# PowerGlove_DueShield.net
KiCad netlist of a schematic drawn in EAGLE
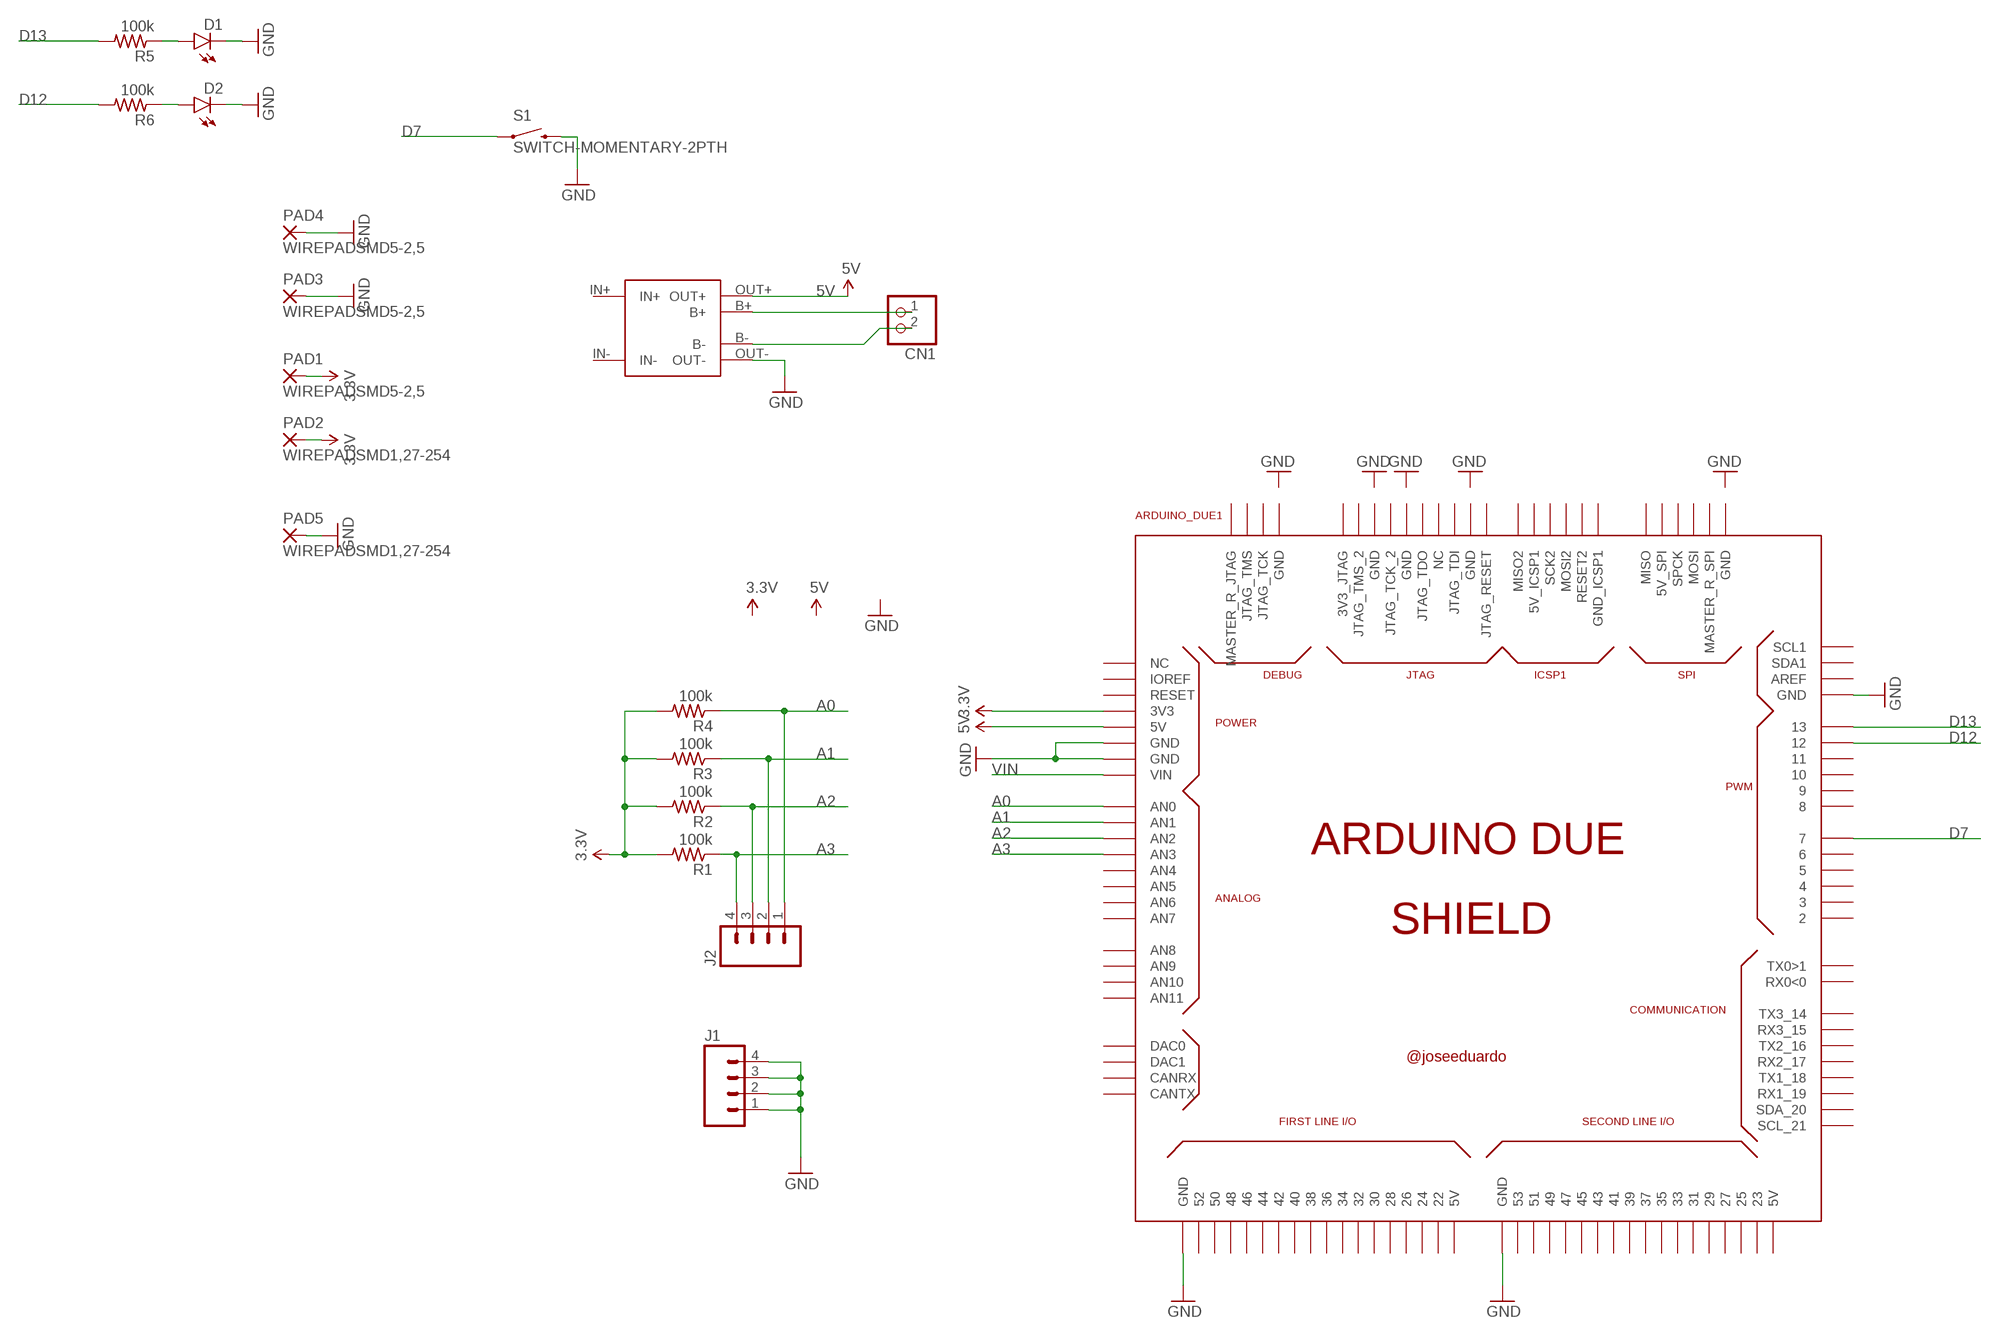
[diagram p0: schematic, sheet 1]

(export (version "E")
  (design (tool "Eeschema 10.0.6"))
  (components
    (comp (ref "ARDUINO_DUE1")
      (value "ARDUINO_DUE_SHIELD")
      (footprint "eagle-import:ARDUINO_DUE_SHIELD")
      (libsource (lib "eagle-import") (part "ARDUINO_DUE_SHIELD"))
    )
    (comp (ref "CN1")
      (value "JST_2PIN-THM-RA")
      (footprint "eagle-import:JST-PH-2-THM-RA")
      (libsource (lib "eagle-import") (part "JST_2PIN-THM-RA"))
    )
    (comp (ref "D1")
      (value "LED3MM")
      (footprint "eagle-import:LED3MM")
      (libsource (lib "eagle-import") (part "LED3MM"))
    )
    (comp (ref "D2")
      (value "LED3MM")
      (footprint "eagle-import:LED3MM")
      (libsource (lib "eagle-import") (part "LED3MM"))
    )
    (comp (ref "J1")
      (value "M04LONGPADS")
      (footprint "eagle-import:1X04_LONGPADS")
      (libsource (lib "eagle-import") (part "M04LONGPADS"))
    )
    (comp (ref "J2")
      (value "M04LONGPADS")
      (footprint "eagle-import:1X04_LONGPADS")
      (libsource (lib "eagle-import") (part "M04LONGPADS"))
    )
    (comp (ref "PAD1")
      (value "WIREPADSMD5-2,5")
      (footprint "eagle-import:5-2,5")
      (libsource (lib "eagle-import") (part "WIREPADSMD5-2,5"))
    )
    (comp (ref "PAD2")
      (value "WIREPADSMD1,27-254")
      (footprint "eagle-import:SMD1,27-2,54")
      (libsource (lib "eagle-import") (part "WIREPADSMD1,27-254"))
    )
    (comp (ref "PAD3")
      (value "WIREPADSMD5-2,5")
      (footprint "eagle-import:5-2,5")
      (libsource (lib "eagle-import") (part "WIREPADSMD5-2,5"))
    )
    (comp (ref "PAD4")
      (value "WIREPADSMD5-2,5")
      (footprint "eagle-import:5-2,5")
      (libsource (lib "eagle-import") (part "WIREPADSMD5-2,5"))
    )
    (comp (ref "PAD5")
      (value "WIREPADSMD1,27-254")
      (footprint "eagle-import:SMD1,27-2,54")
      (libsource (lib "eagle-import") (part "WIREPADSMD1,27-254"))
    )
    (comp (ref "R1")
      (value "100k")
      (footprint "eagle-import:0207_10")
      (libsource (lib "eagle-import") (part "R-US_0207/10"))
    )
    (comp (ref "R2")
      (value "100k")
      (footprint "eagle-import:0207_10")
      (libsource (lib "eagle-import") (part "R-US_0207/10"))
    )
    (comp (ref "R3")
      (value "100k")
      (footprint "eagle-import:0207_10")
      (libsource (lib "eagle-import") (part "R-US_0207/10"))
    )
    (comp (ref "R4")
      (value "100k")
      (footprint "eagle-import:0207_10")
      (libsource (lib "eagle-import") (part "R-US_0207/10"))
    )
    (comp (ref "R5")
      (value "100k")
      (footprint "eagle-import:0207_10")
      (libsource (lib "eagle-import") (part "R-US_0207/10"))
    )
    (comp (ref "R6")
      (value "100k")
      (footprint "eagle-import:0207_10")
      (libsource (lib "eagle-import") (part "R-US_0207/10"))
    )
    (comp (ref "S1")
      (value "SWITCH-MOMENTARY-2PTH")
      (footprint "eagle-import:TACTILE-PTH")
      (libsource (lib "eagle-import") (part "SWITCH-MOMENTARY-2PTH"))
    )
    (comp (ref "U$1")
      (value "TP4056-MODULE")
      (footprint "eagle-import:TP4056-LITHIUM-PROTECTED-MODULE")
      (libsource (lib "eagle-import") (part "TP4056-MODULE"))
    )
  )
  (nets
    (net (code "1") (name "/A0") (class "Default")
      (node (ref "ARDUINO_DUE1") (pin "A0") (pinfunction "AN0_A0") (pintype "bidirectional"))
      (node (ref "J2") (pin "1") (pinfunction "1_1") (pintype "passive"))
      (node (ref "R4") (pin "1") (pinfunction "1_1") (pintype "passive"))
    )
    (net (code "2") (name "/A1") (class "Default")
      (node (ref "ARDUINO_DUE1") (pin "A1") (pinfunction "AN1_A1") (pintype "bidirectional"))
      (node (ref "J2") (pin "2") (pinfunction "2_2") (pintype "passive"))
      (node (ref "R3") (pin "1") (pinfunction "1_1") (pintype "passive"))
    )
    (net (code "3") (name "/A2") (class "Default")
      (node (ref "ARDUINO_DUE1") (pin "A2") (pinfunction "AN2_A2") (pintype "bidirectional"))
      (node (ref "J2") (pin "3") (pinfunction "3_3") (pintype "passive"))
      (node (ref "R2") (pin "1") (pinfunction "1_1") (pintype "passive"))
    )
    (net (code "4") (name "/A3") (class "Default")
      (node (ref "ARDUINO_DUE1") (pin "A3") (pinfunction "AN3_A3") (pintype "bidirectional"))
      (node (ref "J2") (pin "4") (pinfunction "4_4") (pintype "passive"))
      (node (ref "R1") (pin "1") (pinfunction "1_1") (pintype "passive"))
    )
    (net (code "5") (name "/D7") (class "Default")
      (node (ref "ARDUINO_DUE1") (pin "7") (pinfunction "7_7") (pintype "bidirectional"))
      (node (ref "S1") (pin "1") (pinfunction "1_1") (pintype "passive"))
    )
    (net (code "6") (name "/D12") (class "Default")
      (node (ref "ARDUINO_DUE1") (pin "12") (pinfunction "12_12") (pintype "bidirectional"))
      (node (ref "R6") (pin "2") (pinfunction "2_2") (pintype "passive"))
    )
    (net (code "7") (name "/D13") (class "Default")
      (node (ref "ARDUINO_DUE1") (pin "13") (pinfunction "13_13") (pintype "bidirectional"))
      (node (ref "R5") (pin "2") (pinfunction "2_2") (pintype "passive"))
    )
    (net (code "8") (name "/IN+") (class "Default")
      (node (ref "U$1") (pin "IN+") (pinfunction "IN+_IN+") (pintype "power_in"))
    )
    (net (code "9") (name "/IN-") (class "Default")
      (node (ref "U$1") (pin "IN-") (pinfunction "IN-_IN-") (pintype "power_in"))
    )
    (net (code "10") (name "/VIN") (class "Default")
      (node (ref "ARDUINO_DUE1") (pin "VIN") (pinfunction "VIN_VIN") (pintype "bidirectional"))
    )
    (net (code "11") (name "3.3V") (class "Default")
      (node (ref "ARDUINO_DUE1") (pin "3V3") (pinfunction "3V3_3V3") (pintype "bidirectional"))
      (node (ref "PAD1") (pin "1") (pinfunction "P_1") (pintype "passive"))
      (node (ref "PAD2") (pin "1") (pinfunction "P_1") (pintype "passive"))
      (node (ref "R1") (pin "2") (pinfunction "2_2") (pintype "passive"))
      (node (ref "R2") (pin "2") (pinfunction "2_2") (pintype "passive"))
      (node (ref "R3") (pin "2") (pinfunction "2_2") (pintype "passive"))
      (node (ref "R4") (pin "2") (pinfunction "2_2") (pintype "passive"))
    )
    (net (code "12") (name "5V") (class "Default")
      (node (ref "ARDUINO_DUE1") (pin "5V0") (pinfunction "5V_5V0") (pintype "bidirectional"))
      (node (ref "U$1") (pin "OUT+") (pinfunction "OUT+_OUT+") (pintype "power_in"))
    )
    (net (code "13") (name "GND") (class "Default")
      (node (ref "ARDUINO_DUE1") (pin "GND") (pinfunction "GND_GND") (pintype "bidirectional"))
      (node (ref "ARDUINO_DUE1") (pin "GND_1") (pinfunction "GND_GND_1") (pintype "bidirectional"))
      (node (ref "ARDUINO_DUE1") (pin "GND_2") (pinfunction "GND_GND_2") (pintype "bidirectional"))
      (node (ref "ARDUINO_DUE1") (pin "GND_3") (pinfunction "GND_GND_3") (pintype "bidirectional"))
      (node (ref "ARDUINO_DUE1") (pin "GND_4") (pinfunction "GND_GND_4") (pintype "bidirectional"))
      (node (ref "D1") (pin "K") (pinfunction "C_K") (pintype "passive"))
      (node (ref "D2") (pin "K") (pinfunction "C_K") (pintype "passive"))
      (node (ref "J1") (pin "1") (pinfunction "1_1") (pintype "passive"))
      (node (ref "J1") (pin "2") (pinfunction "2_2") (pintype "passive"))
      (node (ref "J1") (pin "3") (pinfunction "3_3") (pintype "passive"))
      (node (ref "J1") (pin "4") (pinfunction "4_4") (pintype "passive"))
      (node (ref "PAD3") (pin "1") (pinfunction "P_1") (pintype "passive"))
      (node (ref "PAD4") (pin "1") (pinfunction "P_1") (pintype "passive"))
      (node (ref "PAD5") (pin "1") (pinfunction "P_1") (pintype "passive"))
      (node (ref "S1") (pin "3") (pinfunction "2_3") (pintype "passive"))
      (node (ref "U$1") (pin "OUT-") (pinfunction "OUT-_OUT-") (pintype "power_in"))
    )
    (net (code "14") (name "Net-(CN1-1)") (class "Default")
      (node (ref "CN1") (pin "2") (pinfunction "1_2") (pintype "passive"))
      (node (ref "U$1") (pin "B-") (pinfunction "B-_B-") (pintype "power_in"))
    )
    (net (code "15") (name "Net-(CN1-2)") (class "Default")
      (node (ref "CN1") (pin "1") (pinfunction "2_1") (pintype "passive"))
      (node (ref "U$1") (pin "B+") (pinfunction "B+_B+") (pintype "power_in"))
    )
    (net (code "16") (name "Net-(D1-PadA)") (class "Default")
      (node (ref "D1") (pin "A") (pinfunction "A_A") (pintype "passive"))
      (node (ref "R5") (pin "1") (pinfunction "1_1") (pintype "passive"))
    )
    (net (code "17") (name "Net-(D2-PadA)") (class "Default")
      (node (ref "D2") (pin "A") (pinfunction "A_A") (pintype "passive"))
      (node (ref "R6") (pin "1") (pinfunction "1_1") (pintype "passive"))
    )
    (net (code "18") (name "unconnected-(ARDUINO_DUE1-5V-Pad5V0_1)") (class "Default")
      (node (ref "ARDUINO_DUE1") (pin "5V0_1") (pinfunction "5V_5V0_1") (pintype "bidirectional"))
    )
    (net (code "19") (name "unconnected-(ARDUINO_DUE1-5V-Pad5V0_2)") (class "Default")
      (node (ref "ARDUINO_DUE1") (pin "5V0_2") (pinfunction "5V_5V0_2") (pintype "bidirectional"))
    )
    (net (code "20") (name "unconnected-(ARDUINO_DUE1-5V_SPI-Pad5V_2)") (class "Default")
      (node (ref "ARDUINO_DUE1") (pin "5V_2") (pinfunction "5V_SPI_5V_2") (pintype "bidirectional"))
    )
    (net (code "21") (name "unconnected-(ARDUINO_DUE1-AN4-PadA4)") (class "Default")
      (node (ref "ARDUINO_DUE1") (pin "A4") (pinfunction "AN4_A4") (pintype "bidirectional"))
    )
    (net (code "22") (name "unconnected-(ARDUINO_DUE1-AN5-PadA5)") (class "Default")
      (node (ref "ARDUINO_DUE1") (pin "A5") (pinfunction "AN5_A5") (pintype "bidirectional"))
    )
    (net (code "23") (name "unconnected-(ARDUINO_DUE1-AN6-PadA6)") (class "Default")
      (node (ref "ARDUINO_DUE1") (pin "A6") (pinfunction "AN6_A6") (pintype "bidirectional"))
    )
    (net (code "24") (name "unconnected-(ARDUINO_DUE1-AN7-PadA7)") (class "Default")
      (node (ref "ARDUINO_DUE1") (pin "A7") (pinfunction "AN7_A7") (pintype "bidirectional"))
    )
    (net (code "25") (name "unconnected-(ARDUINO_DUE1-AN8-PadA8)") (class "Default")
      (node (ref "ARDUINO_DUE1") (pin "A8") (pinfunction "AN8_A8") (pintype "bidirectional"))
    )
    (net (code "26") (name "unconnected-(ARDUINO_DUE1-AN9-PadA9)") (class "Default")
      (node (ref "ARDUINO_DUE1") (pin "A9") (pinfunction "AN9_A9") (pintype "bidirectional"))
    )
    (net (code "27") (name "unconnected-(ARDUINO_DUE1-AN10-PadA10)") (class "Default")
      (node (ref "ARDUINO_DUE1") (pin "A10") (pinfunction "AN10_A10") (pintype "bidirectional"))
    )
    (net (code "28") (name "unconnected-(ARDUINO_DUE1-AN11-PadA11)") (class "Default")
      (node (ref "ARDUINO_DUE1") (pin "A11") (pinfunction "AN11_A11") (pintype "bidirectional"))
    )
    (net (code "29") (name "unconnected-(ARDUINO_DUE1-GND-PadGND_5)") (class "Default")
      (node (ref "ARDUINO_DUE1") (pin "GND_5") (pinfunction "GND_GND_5") (pintype "bidirectional"))
    )
    (net (code "30") (name "unconnected-(ARDUINO_DUE1-GND-PadGND_7)") (class "Default")
      (node (ref "ARDUINO_DUE1") (pin "GND_7") (pinfunction "GND_GND_7") (pintype "bidirectional"))
    )
    (net (code "31") (name "unconnected-(ARDUINO_DUE1-GND-PadGND_8)") (class "Default")
      (node (ref "ARDUINO_DUE1") (pin "GND_8") (pinfunction "GND_GND_8") (pintype "bidirectional"))
    )
    (net (code "32") (name "unconnected-(ARDUINO_DUE1-GND-PadGND_9)") (class "Default")
      (node (ref "ARDUINO_DUE1") (pin "GND_9") (pinfunction "GND_GND_9") (pintype "bidirectional"))
    )
    (net (code "33") (name "unconnected-(ARDUINO_DUE1-GND-PadGND_10)") (class "Default")
      (node (ref "ARDUINO_DUE1") (pin "GND_10") (pinfunction "GND_GND_10") (pintype "bidirectional"))
    )
    (net (code "34") (name "unconnected-(ARDUINO_DUE1-MASTER_R_JTAG-PadMASTER_RESET_JTAG)") (class "Default")
      (node (ref "ARDUINO_DUE1") (pin "MASTER_RESET_JTAG") (pinfunction "MASTER_R_JTAG_MASTER_RESET_JTAG") (pintype "bidirectional"))
    )
    (net (code "35") (name "unconnected-(ARDUINO_DUE1-MASTER_R_SPI-PadMASTER_RESET_SPI)") (class "Default")
      (node (ref "ARDUINO_DUE1") (pin "MASTER_RESET_SPI") (pinfunction "MASTER_R_SPI_MASTER_RESET_SPI") (pintype "bidirectional"))
    )
    (net (code "36") (name "unconnected-(ARDUINO_DUE1-NC-PadNC_2)") (class "Default")
      (node (ref "ARDUINO_DUE1") (pin "NC_2") (pinfunction "NC_NC_2") (pintype "no_connect"))
    )
    (net (code "37") (name "unconnected-(ARDUINO_DUE1-NC-PadNC_5)") (class "Default")
      (node (ref "ARDUINO_DUE1") (pin "NC_5") (pinfunction "NC_NC_5") (pintype "bidirectional"))
    )
    (net (code "38") (name "unconnected-(ARDUINO_DUE1-Pad2)") (class "Default")
      (node (ref "ARDUINO_DUE1") (pin "2") (pinfunction "2_2") (pintype "bidirectional"))
    )
    (net (code "39") (name "unconnected-(ARDUINO_DUE1-Pad3)") (class "Default")
      (node (ref "ARDUINO_DUE1") (pin "3") (pinfunction "3_3") (pintype "bidirectional"))
    )
    (net (code "40") (name "unconnected-(ARDUINO_DUE1-Pad3V3_JTAG)") (class "Default")
      (node (ref "ARDUINO_DUE1") (pin "3V3_JTAG") (pinfunction "3V3_JTAG_3V3_JTAG") (pintype "bidirectional"))
    )
    (net (code "41") (name "unconnected-(ARDUINO_DUE1-Pad4)") (class "Default")
      (node (ref "ARDUINO_DUE1") (pin "4") (pinfunction "4_4") (pintype "bidirectional"))
    )
    (net (code "42") (name "unconnected-(ARDUINO_DUE1-Pad5)") (class "Default")
      (node (ref "ARDUINO_DUE1") (pin "5") (pinfunction "5_5") (pintype "bidirectional"))
    )
    (net (code "43") (name "unconnected-(ARDUINO_DUE1-Pad5V_ICSP1)") (class "Default")
      (node (ref "ARDUINO_DUE1") (pin "5V_ICSP1") (pinfunction "5V_ICSP1_5V_ICSP1") (pintype "bidirectional"))
    )
    (net (code "44") (name "unconnected-(ARDUINO_DUE1-Pad6)") (class "Default")
      (node (ref "ARDUINO_DUE1") (pin "6") (pinfunction "6_6") (pintype "bidirectional"))
    )
    (net (code "45") (name "unconnected-(ARDUINO_DUE1-Pad8)") (class "Default")
      (node (ref "ARDUINO_DUE1") (pin "8") (pinfunction "8_8") (pintype "bidirectional"))
    )
    (net (code "46") (name "unconnected-(ARDUINO_DUE1-Pad9)") (class "Default")
      (node (ref "ARDUINO_DUE1") (pin "9") (pinfunction "9_9") (pintype "bidirectional"))
    )
    (net (code "47") (name "unconnected-(ARDUINO_DUE1-Pad10)") (class "Default")
      (node (ref "ARDUINO_DUE1") (pin "10") (pinfunction "10_10") (pintype "bidirectional"))
    )
    (net (code "48") (name "unconnected-(ARDUINO_DUE1-Pad11)") (class "Default")
      (node (ref "ARDUINO_DUE1") (pin "11") (pinfunction "11_11") (pintype "bidirectional"))
    )
    (net (code "49") (name "unconnected-(ARDUINO_DUE1-Pad22)") (class "Default")
      (node (ref "ARDUINO_DUE1") (pin "22") (pinfunction "22_22") (pintype "bidirectional"))
    )
    (net (code "50") (name "unconnected-(ARDUINO_DUE1-Pad23)") (class "Default")
      (node (ref "ARDUINO_DUE1") (pin "23") (pinfunction "23_23") (pintype "bidirectional"))
    )
    (net (code "51") (name "unconnected-(ARDUINO_DUE1-Pad24)") (class "Default")
      (node (ref "ARDUINO_DUE1") (pin "24") (pinfunction "24_24") (pintype "bidirectional"))
    )
    (net (code "52") (name "unconnected-(ARDUINO_DUE1-Pad25)") (class "Default")
      (node (ref "ARDUINO_DUE1") (pin "25") (pinfunction "25_25") (pintype "bidirectional"))
    )
    (net (code "53") (name "unconnected-(ARDUINO_DUE1-Pad26)") (class "Default")
      (node (ref "ARDUINO_DUE1") (pin "26") (pinfunction "26_26") (pintype "bidirectional"))
    )
    (net (code "54") (name "unconnected-(ARDUINO_DUE1-Pad27)") (class "Default")
      (node (ref "ARDUINO_DUE1") (pin "27") (pinfunction "27_27") (pintype "bidirectional"))
    )
    (net (code "55") (name "unconnected-(ARDUINO_DUE1-Pad28)") (class "Default")
      (node (ref "ARDUINO_DUE1") (pin "28") (pinfunction "28_28") (pintype "bidirectional"))
    )
    (net (code "56") (name "unconnected-(ARDUINO_DUE1-Pad29)") (class "Default")
      (node (ref "ARDUINO_DUE1") (pin "29") (pinfunction "29_29") (pintype "bidirectional"))
    )
    (net (code "57") (name "unconnected-(ARDUINO_DUE1-Pad30)") (class "Default")
      (node (ref "ARDUINO_DUE1") (pin "30") (pinfunction "30_30") (pintype "bidirectional"))
    )
    (net (code "58") (name "unconnected-(ARDUINO_DUE1-Pad31)") (class "Default")
      (node (ref "ARDUINO_DUE1") (pin "31") (pinfunction "31_31") (pintype "bidirectional"))
    )
    (net (code "59") (name "unconnected-(ARDUINO_DUE1-Pad32)") (class "Default")
      (node (ref "ARDUINO_DUE1") (pin "32") (pinfunction "32_32") (pintype "bidirectional"))
    )
    (net (code "60") (name "unconnected-(ARDUINO_DUE1-Pad33)") (class "Default")
      (node (ref "ARDUINO_DUE1") (pin "33") (pinfunction "33_33") (pintype "bidirectional"))
    )
    (net (code "61") (name "unconnected-(ARDUINO_DUE1-Pad34)") (class "Default")
      (node (ref "ARDUINO_DUE1") (pin "34") (pinfunction "34_34") (pintype "bidirectional"))
    )
    (net (code "62") (name "unconnected-(ARDUINO_DUE1-Pad35)") (class "Default")
      (node (ref "ARDUINO_DUE1") (pin "35") (pinfunction "35_35") (pintype "bidirectional"))
    )
    (net (code "63") (name "unconnected-(ARDUINO_DUE1-Pad36)") (class "Default")
      (node (ref "ARDUINO_DUE1") (pin "36") (pinfunction "36_36") (pintype "bidirectional"))
    )
    (net (code "64") (name "unconnected-(ARDUINO_DUE1-Pad37)") (class "Default")
      (node (ref "ARDUINO_DUE1") (pin "37") (pinfunction "37_37") (pintype "bidirectional"))
    )
    (net (code "65") (name "unconnected-(ARDUINO_DUE1-Pad38)") (class "Default")
      (node (ref "ARDUINO_DUE1") (pin "38") (pinfunction "38_38") (pintype "bidirectional"))
    )
    (net (code "66") (name "unconnected-(ARDUINO_DUE1-Pad39)") (class "Default")
      (node (ref "ARDUINO_DUE1") (pin "39") (pinfunction "39_39") (pintype "bidirectional"))
    )
    (net (code "67") (name "unconnected-(ARDUINO_DUE1-Pad40)") (class "Default")
      (node (ref "ARDUINO_DUE1") (pin "40") (pinfunction "40_40") (pintype "bidirectional"))
    )
    (net (code "68") (name "unconnected-(ARDUINO_DUE1-Pad41)") (class "Default")
      (node (ref "ARDUINO_DUE1") (pin "41") (pinfunction "41_41") (pintype "bidirectional"))
    )
    (net (code "69") (name "unconnected-(ARDUINO_DUE1-Pad42)") (class "Default")
      (node (ref "ARDUINO_DUE1") (pin "42") (pinfunction "42_42") (pintype "bidirectional"))
    )
    (net (code "70") (name "unconnected-(ARDUINO_DUE1-Pad43)") (class "Default")
      (node (ref "ARDUINO_DUE1") (pin "43") (pinfunction "43_43") (pintype "bidirectional"))
    )
    (net (code "71") (name "unconnected-(ARDUINO_DUE1-Pad44)") (class "Default")
      (node (ref "ARDUINO_DUE1") (pin "44") (pinfunction "44_44") (pintype "bidirectional"))
    )
    (net (code "72") (name "unconnected-(ARDUINO_DUE1-Pad45)") (class "Default")
      (node (ref "ARDUINO_DUE1") (pin "45") (pinfunction "45_45") (pintype "bidirectional"))
    )
    (net (code "73") (name "unconnected-(ARDUINO_DUE1-Pad46)") (class "Default")
      (node (ref "ARDUINO_DUE1") (pin "46") (pinfunction "46_46") (pintype "bidirectional"))
    )
    (net (code "74") (name "unconnected-(ARDUINO_DUE1-Pad47)") (class "Default")
      (node (ref "ARDUINO_DUE1") (pin "47") (pinfunction "47_47") (pintype "bidirectional"))
    )
    (net (code "75") (name "unconnected-(ARDUINO_DUE1-Pad48)") (class "Default")
      (node (ref "ARDUINO_DUE1") (pin "48") (pinfunction "48_48") (pintype "bidirectional"))
    )
    (net (code "76") (name "unconnected-(ARDUINO_DUE1-Pad49)") (class "Default")
      (node (ref "ARDUINO_DUE1") (pin "49") (pinfunction "49_49") (pintype "bidirectional"))
    )
    (net (code "77") (name "unconnected-(ARDUINO_DUE1-Pad50)") (class "Default")
      (node (ref "ARDUINO_DUE1") (pin "50") (pinfunction "50_50") (pintype "bidirectional"))
    )
    (net (code "78") (name "unconnected-(ARDUINO_DUE1-Pad51)") (class "Default")
      (node (ref "ARDUINO_DUE1") (pin "51") (pinfunction "51_51") (pintype "bidirectional"))
    )
    (net (code "79") (name "unconnected-(ARDUINO_DUE1-Pad52)") (class "Default")
      (node (ref "ARDUINO_DUE1") (pin "52") (pinfunction "52_52") (pintype "bidirectional"))
    )
    (net (code "80") (name "unconnected-(ARDUINO_DUE1-Pad53)") (class "Default")
      (node (ref "ARDUINO_DUE1") (pin "53") (pinfunction "53_53") (pintype "bidirectional"))
    )
    (net (code "81") (name "unconnected-(ARDUINO_DUE1-PadAREF)") (class "Default")
      (node (ref "ARDUINO_DUE1") (pin "AREF") (pinfunction "AREF_AREF") (pintype "bidirectional"))
    )
    (net (code "82") (name "unconnected-(ARDUINO_DUE1-PadCANRX)") (class "Default")
      (node (ref "ARDUINO_DUE1") (pin "CANRX") (pinfunction "CANRX_CANRX") (pintype "bidirectional"))
    )
    (net (code "83") (name "unconnected-(ARDUINO_DUE1-PadCANTX)") (class "Default")
      (node (ref "ARDUINO_DUE1") (pin "CANTX") (pinfunction "CANTX_CANTX") (pintype "bidirectional"))
    )
    (net (code "84") (name "unconnected-(ARDUINO_DUE1-PadDAC0)") (class "Default")
      (node (ref "ARDUINO_DUE1") (pin "DAC0") (pinfunction "DAC0_DAC0") (pintype "bidirectional"))
    )
    (net (code "85") (name "unconnected-(ARDUINO_DUE1-PadDAC1)") (class "Default")
      (node (ref "ARDUINO_DUE1") (pin "DAC1") (pinfunction "DAC1_DAC1") (pintype "bidirectional"))
    )
    (net (code "86") (name "unconnected-(ARDUINO_DUE1-PadGND_ICSP1)") (class "Default")
      (node (ref "ARDUINO_DUE1") (pin "GND_ICSP1") (pinfunction "GND_ICSP1_GND_ICSP1") (pintype "bidirectional"))
    )
    (net (code "87") (name "unconnected-(ARDUINO_DUE1-PadIOREF)") (class "Default")
      (node (ref "ARDUINO_DUE1") (pin "IOREF") (pinfunction "IOREF_IOREF") (pintype "bidirectional"))
    )
    (net (code "88") (name "unconnected-(ARDUINO_DUE1-PadJTAG_RESET)") (class "Default")
      (node (ref "ARDUINO_DUE1") (pin "JTAG_RESET") (pinfunction "JTAG_RESET_JTAG_RESET") (pintype "bidirectional"))
    )
    (net (code "89") (name "unconnected-(ARDUINO_DUE1-PadJTAG_TCK)") (class "Default")
      (node (ref "ARDUINO_DUE1") (pin "JTAG_TCK") (pinfunction "JTAG_TCK_JTAG_TCK") (pintype "bidirectional"))
    )
    (net (code "90") (name "unconnected-(ARDUINO_DUE1-PadJTAG_TCK_2)") (class "Default")
      (node (ref "ARDUINO_DUE1") (pin "JTAG_TCK_2") (pinfunction "JTAG_TCK_2_JTAG_TCK_2") (pintype "bidirectional"))
    )
    (net (code "91") (name "unconnected-(ARDUINO_DUE1-PadJTAG_TDI)") (class "Default")
      (node (ref "ARDUINO_DUE1") (pin "JTAG_TDI") (pinfunction "JTAG_TDI_JTAG_TDI") (pintype "bidirectional"))
    )
    (net (code "92") (name "unconnected-(ARDUINO_DUE1-PadJTAG_TDO)") (class "Default")
      (node (ref "ARDUINO_DUE1") (pin "JTAG_TDO") (pinfunction "JTAG_TDO_JTAG_TDO") (pintype "bidirectional"))
    )
    (net (code "93") (name "unconnected-(ARDUINO_DUE1-PadJTAG_TMS)") (class "Default")
      (node (ref "ARDUINO_DUE1") (pin "JTAG_TMS") (pinfunction "JTAG_TMS_JTAG_TMS") (pintype "bidirectional"))
    )
    (net (code "94") (name "unconnected-(ARDUINO_DUE1-PadJTAG_TMS_2)") (class "Default")
      (node (ref "ARDUINO_DUE1") (pin "JTAG_TMS_2") (pinfunction "JTAG_TMS_2_JTAG_TMS_2") (pintype "bidirectional"))
    )
    (net (code "95") (name "unconnected-(ARDUINO_DUE1-PadMISO)") (class "Default")
      (node (ref "ARDUINO_DUE1") (pin "MISO") (pinfunction "MISO_MISO") (pintype "bidirectional"))
    )
    (net (code "96") (name "unconnected-(ARDUINO_DUE1-PadMISO2)") (class "Default")
      (node (ref "ARDUINO_DUE1") (pin "MISO2") (pinfunction "MISO2_MISO2") (pintype "bidirectional"))
    )
    (net (code "97") (name "unconnected-(ARDUINO_DUE1-PadMOSI)") (class "Default")
      (node (ref "ARDUINO_DUE1") (pin "MOSI") (pinfunction "MOSI_MOSI") (pintype "bidirectional"))
    )
    (net (code "98") (name "unconnected-(ARDUINO_DUE1-PadMOSI2)") (class "Default")
      (node (ref "ARDUINO_DUE1") (pin "MOSI2") (pinfunction "MOSI2_MOSI2") (pintype "bidirectional"))
    )
    (net (code "99") (name "unconnected-(ARDUINO_DUE1-PadRESET)") (class "Default")
      (node (ref "ARDUINO_DUE1") (pin "RESET") (pinfunction "RESET_RESET") (pintype "bidirectional"))
    )
    (net (code "100") (name "unconnected-(ARDUINO_DUE1-PadRESET2)") (class "Default")
      (node (ref "ARDUINO_DUE1") (pin "RESET2") (pinfunction "RESET2_RESET2") (pintype "bidirectional"))
    )
    (net (code "101") (name "unconnected-(ARDUINO_DUE1-PadSCK2)") (class "Default")
      (node (ref "ARDUINO_DUE1") (pin "SCK2") (pinfunction "SCK2_SCK2") (pintype "bidirectional"))
    )
    (net (code "102") (name "unconnected-(ARDUINO_DUE1-PadSCL1)") (class "Default")
      (node (ref "ARDUINO_DUE1") (pin "SCL1") (pinfunction "SCL1_SCL1") (pintype "bidirectional"))
    )
    (net (code "103") (name "unconnected-(ARDUINO_DUE1-PadSDA1)") (class "Default")
      (node (ref "ARDUINO_DUE1") (pin "SDA1") (pinfunction "SDA1_SDA1") (pintype "bidirectional"))
    )
    (net (code "104") (name "unconnected-(ARDUINO_DUE1-PadSPCK)") (class "Default")
      (node (ref "ARDUINO_DUE1") (pin "SPCK") (pinfunction "SPCK_SPCK") (pintype "bidirectional"))
    )
    (net (code "105") (name "unconnected-(ARDUINO_DUE1-RX0<0-Pad0)") (class "Default")
      (node (ref "ARDUINO_DUE1") (pin "0") (pinfunction "RX0<0_0") (pintype "bidirectional"))
    )
    (net (code "106") (name "unconnected-(ARDUINO_DUE1-RX1_19-Pad19)") (class "Default")
      (node (ref "ARDUINO_DUE1") (pin "19") (pinfunction "RX1_19_19") (pintype "bidirectional"))
    )
    (net (code "107") (name "unconnected-(ARDUINO_DUE1-RX2_17-Pad17)") (class "Default")
      (node (ref "ARDUINO_DUE1") (pin "17") (pinfunction "RX2_17_17") (pintype "bidirectional"))
    )
    (net (code "108") (name "unconnected-(ARDUINO_DUE1-RX3_15-Pad15)") (class "Default")
      (node (ref "ARDUINO_DUE1") (pin "15") (pinfunction "RX3_15_15") (pintype "bidirectional"))
    )
    (net (code "109") (name "unconnected-(ARDUINO_DUE1-SCL_21-Pad21)") (class "Default")
      (node (ref "ARDUINO_DUE1") (pin "21") (pinfunction "SCL_21_21") (pintype "bidirectional"))
    )
    (net (code "110") (name "unconnected-(ARDUINO_DUE1-SDA_20-Pad20)") (class "Default")
      (node (ref "ARDUINO_DUE1") (pin "20") (pinfunction "SDA_20_20") (pintype "bidirectional"))
    )
    (net (code "111") (name "unconnected-(ARDUINO_DUE1-TX0>1-Pad1)") (class "Default")
      (node (ref "ARDUINO_DUE1") (pin "1") (pinfunction "TX0>1_1") (pintype "bidirectional"))
    )
    (net (code "112") (name "unconnected-(ARDUINO_DUE1-TX1_18-Pad18)") (class "Default")
      (node (ref "ARDUINO_DUE1") (pin "18") (pinfunction "TX1_18_18") (pintype "bidirectional"))
    )
    (net (code "113") (name "unconnected-(ARDUINO_DUE1-TX2_16-Pad16)") (class "Default")
      (node (ref "ARDUINO_DUE1") (pin "16") (pinfunction "TX2_16_16") (pintype "bidirectional"))
    )
    (net (code "114") (name "unconnected-(ARDUINO_DUE1-TX3_14-Pad14)") (class "Default")
      (node (ref "ARDUINO_DUE1") (pin "14") (pinfunction "TX3_14_14") (pintype "bidirectional"))
    )
  )
)
